# PolarizacionBJT.net
KiCad netlist of a schematic drawn in Altium Designer
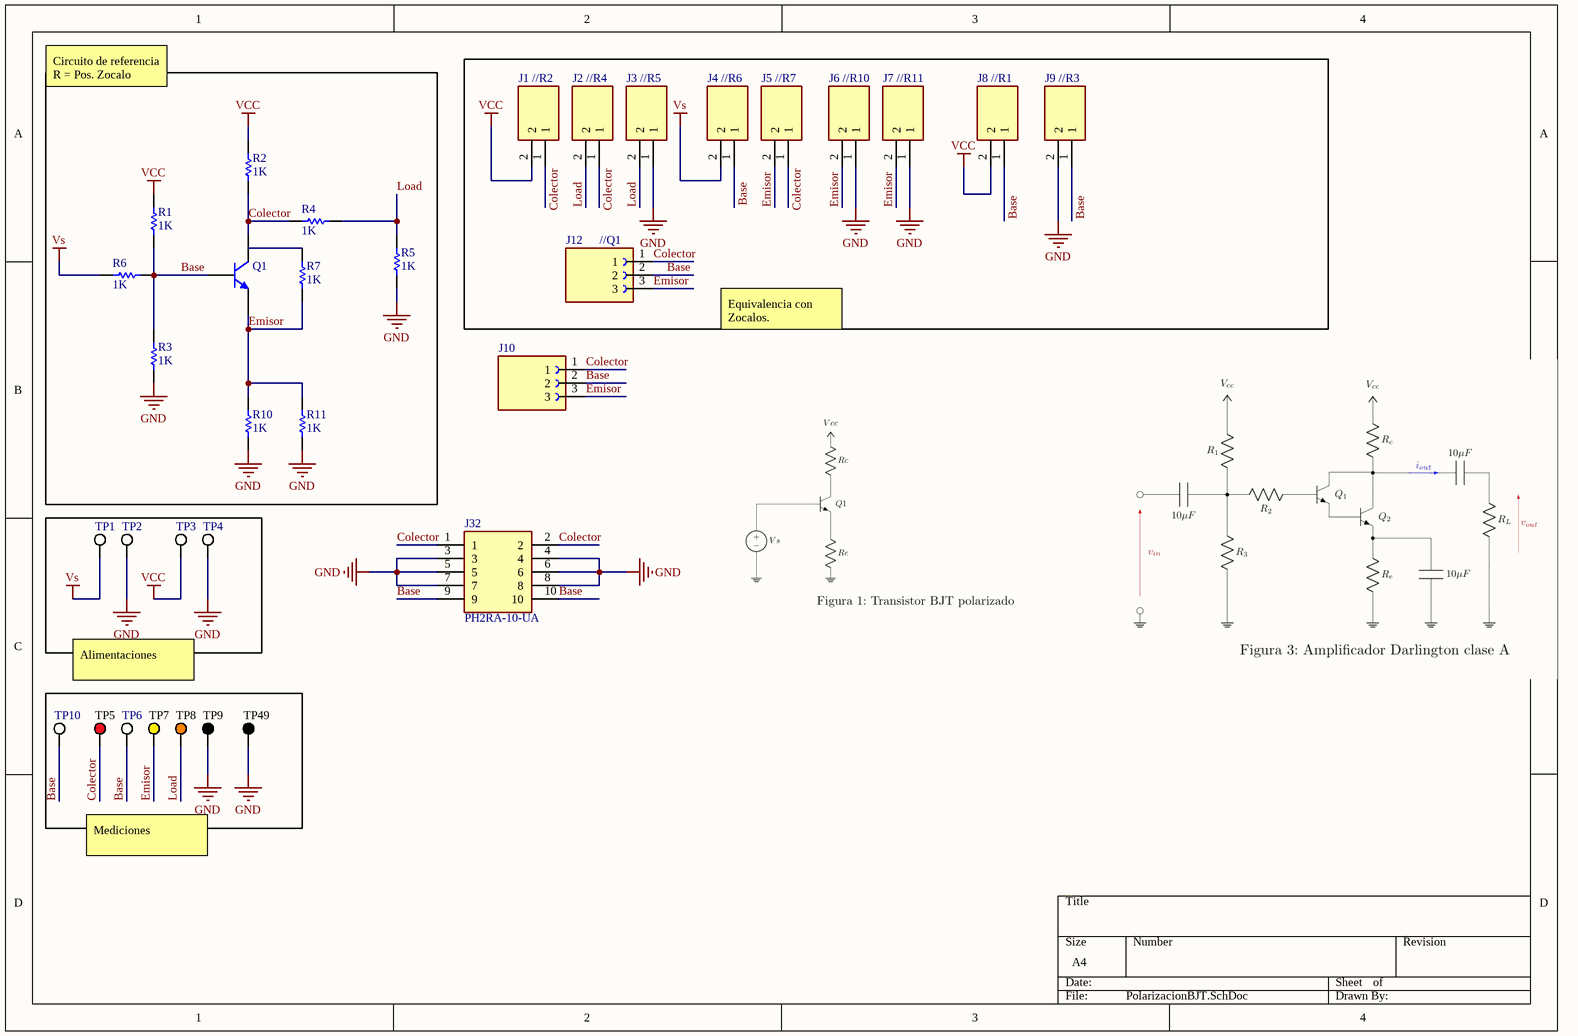
[diagram p0: PolarizacionBJT.SchDoc]

(export (version "E")
  (design (tool "Eeschema 10.0.6"))
  (components
    (comp (ref "J1")
      (value "D01-9970242")
      (footprint "D019970242")
      (description "IC Socket: 2 Pos Receptacle SIL Straight THT Strip")
      (fields (field (name "MOUSER PART NUMBER") "855-D01-9970242"))
      (libsource (lib "Zocalo_2pines") (part "D01-9970242"))
    )
    (comp (ref "J2")
      (value "D01-9970242")
      (footprint "D019970242")
      (description "IC Socket: 2 Pos Receptacle SIL Straight THT Strip")
      (fields (field (name "MOUSER PART NUMBER") "855-D01-9970242"))
      (libsource (lib "Zocalo_2pines") (part "D01-9970242"))
    )
    (comp (ref "J3")
      (value "D01-9970242")
      (footprint "D019970242")
      (description "IC Socket: 2 Pos Receptacle SIL Straight THT Strip")
      (fields (field (name "MOUSER PART NUMBER") "855-D01-9970242"))
      (libsource (lib "Zocalo_2pines") (part "D01-9970242"))
    )
    (comp (ref "J4")
      (value "D01-9970242")
      (footprint "D019970242")
      (description "IC Socket: 2 Pos Receptacle SIL Straight THT Strip")
      (fields (field (name "MOUSER PART NUMBER") "855-D01-9970242"))
      (libsource (lib "Zocalo_2pines") (part "D01-9970242"))
    )
    (comp (ref "J5")
      (value "D01-9970242")
      (footprint "D019970242")
      (description "IC Socket: 2 Pos Receptacle SIL Straight THT Strip")
      (fields (field (name "MOUSER PART NUMBER") "855-D01-9970242"))
      (libsource (lib "Zocalo_2pines") (part "D01-9970242"))
    )
    (comp (ref "J6")
      (value "D01-9970242")
      (footprint "D019970242")
      (description "IC Socket: 2 Pos Receptacle SIL Straight THT Strip")
      (fields (field (name "MOUSER PART NUMBER") "855-D01-9970242"))
      (libsource (lib "Zocalo_2pines") (part "D01-9970242"))
    )
    (comp (ref "J7")
      (value "D01-9970242")
      (footprint "D019970242")
      (description "IC Socket: 2 Pos Receptacle SIL Straight THT Strip")
      (fields (field (name "MOUSER PART NUMBER") "855-D01-9970242"))
      (libsource (lib "Zocalo_2pines") (part "D01-9970242"))
    )
    (comp (ref "J8")
      (value "D01-9970242")
      (footprint "D019970242")
      (description "IC Socket: 2 Pos Receptacle SIL Straight THT Strip")
      (fields (field (name "MOUSER PART NUMBER") "855-D01-9970242"))
      (libsource (lib "Zocalo_2pines") (part "D01-9970242"))
    )
    (comp (ref "J9")
      (value "D01-9970242")
      (footprint "D019970242")
      (description "IC Socket: 2 Pos Receptacle SIL Straight THT Strip")
      (fields (field (name "MOUSER PART NUMBER") "855-D01-9970242"))
      (libsource (lib "Zocalo_2pines") (part "D01-9970242"))
    )
    (comp (ref "J10")
      (value "D01-9970342")
      (footprint "HARWIN_D01-9970342")
      (libsource (lib "Zocalo_3pines") (part "D01-9970342"))
    )
    (comp (ref "J12")
      (value "D01-9970342")
      (footprint "HARWIN_D01-9970342")
      (libsource (lib "Zocalo_3pines") (part "D01-9970342"))
    )
    (comp (ref "J32")
      (value "PH2RA-10-UA")
      (footprint "HDRRA10W64P254_2X5_1270X250X538P")
      (description "CONN HEADER R/A 10POS 2.54MM")
      (fields (field (name "MOUSER PART NUMBER") "737-PH2RA-10-UA"))
      (libsource (lib "PH2RA-10-UA") (part "PH2RA-10-UA"))
    )
    (comp (ref "Q1")
      (value "Bipolar NPN 3 Pins Transistor VBIC Model")
      (libsource (lib "Simulation Generic Components") (part "BJT NPN VBIC"))
    )
    (comp (ref "R1")
      (value "1K")
      (description "Resistor")
      (libsource (lib "Simulation Generic Components") (part "Resistor"))
    )
    (comp (ref "R2")
      (value "1K")
      (description "Resistor")
      (libsource (lib "Simulation Generic Components") (part "Resistor"))
    )
    (comp (ref "R3")
      (value "1K")
      (description "Resistor")
      (libsource (lib "Simulation Generic Components") (part "Resistor"))
    )
    (comp (ref "R4")
      (value "1K")
      (description "Resistor")
      (libsource (lib "Simulation Generic Components") (part "Resistor"))
    )
    (comp (ref "R5")
      (value "1K")
      (description "Resistor")
      (libsource (lib "Simulation Generic Components") (part "Resistor"))
    )
    (comp (ref "R6")
      (value "1K")
      (description "Resistor")
      (libsource (lib "Simulation Generic Components") (part "Resistor"))
    )
    (comp (ref "R7")
      (value "1K")
      (description "Resistor")
      (libsource (lib "Simulation Generic Components") (part "Resistor"))
    )
    (comp (ref "R10")
      (value "1K")
      (description "Resistor")
      (libsource (lib "Simulation Generic Components") (part "Resistor"))
    )
    (comp (ref "R11")
      (value "1K")
      (description "Resistor")
      (libsource (lib "Simulation Generic Components") (part "Resistor"))
    )
    (comp (ref "TP1")
      (value "575-4")
      (footprint "KSTN-575-4")
      (description "Banana Jack, Non-Insulated, 1-Pin THD, RoHS, Bulk")
      (fields (field (name "MANUFACTURER") "Keystone-Electronics"))
      (libsource (lib "Altium Content Vault") (part "TESTPOINT_WHITE"))
    )
    (comp (ref "TP2")
      (value "575-4")
      (footprint "KSTN-575-4")
      (description "Banana Jack, Non-Insulated, 1-Pin THD, RoHS, Bulk")
      (fields (field (name "MANUFACTURER") "Keystone-Electronics"))
      (libsource (lib "Altium Content Vault") (part "TESTPOINT_WHITE"))
    )
    (comp (ref "TP3")
      (value "575-4")
      (footprint "KSTN-575-4")
      (description "Banana Jack, Non-Insulated, 1-Pin THD, RoHS, Bulk")
      (fields (field (name "MANUFACTURER") "Keystone-Electronics"))
      (libsource (lib "Altium Content Vault") (part "TESTPOINT_WHITE"))
    )
    (comp (ref "TP4")
      (value "575-4")
      (footprint "KSTN-575-4")
      (description "Banana Jack, Non-Insulated, 1-Pin THD, RoHS, Bulk")
      (fields (field (name "MANUFACTURER") "Keystone-Electronics"))
      (libsource (lib "Altium Content Vault") (part "TESTPOINT_WHITE"))
    )
    (comp (ref "TP5")
      (value "5010")
      (footprint "KSTN-5010_V")
      (description "Test Point, Red, Through Hole, RoHS, Bulk")
      (fields (field (name "MANUFACTURER") "Keystone"))
      (libsource (lib "Altium Content Vault") (part "TESTPOINT_RED"))
    )
    (comp (ref "TP6")
      (value "5012")
      (footprint "KSTN-5012_V")
      (description "Test Point, White, Through Hole, RoHS, Bulk")
      (fields (field (name "MANUFACTURER") "Keystone"))
      (libsource (lib "Altium Content Vault") (part "TESTPOINT_WHITE"))
    )
    (comp (ref "TP7")
      (value "5014")
      (footprint "KSTN-5014_V")
      (description "Test Point, Yellow, Through Hole, RoHS, Bulk")
      (fields (field (name "MANUFACTURER") "Keystone"))
      (libsource (lib "Altium Content Vault") (part "TESTPOINT_YELLOW"))
    )
    (comp (ref "TP8")
      (value "5013")
      (footprint "KSTN-5013_V")
      (description "Test Point, Orange, Through Hole, RoHS, Bulk")
      (fields (field (name "MANUFACTURER") "Keystone"))
      (libsource (lib "Altium Content Vault") (part "TESTPOINT_ORANGE"))
    )
    (comp (ref "TP9")
      (value "5011")
      (footprint "KSTN-5011_V")
      (description "Test Point, Black, Through Hole, RoHS, Bulk")
      (fields (field (name "MANUFACTURER") "Keystone"))
      (libsource (lib "Altium Content Vault") (part "TESTPOINT_BLACK"))
    )
    (comp (ref "TP10")
      (value "5012")
      (footprint "KSTN-5012_V")
      (description "Test Point, White, Through Hole, RoHS, Bulk")
      (fields (field (name "MANUFACTURER") "Keystone"))
      (libsource (lib "Altium Content Vault") (part "TESTPOINT_WHITE"))
    )
    (comp (ref "TP49")
      (value "5011")
      (footprint "KSTN-5011_V")
      (description "Test Point, Black, Through Hole, RoHS, Bulk")
      (fields (field (name "MANUFACTURER") "Keystone"))
      (libsource (lib "Altium Content Vault") (part "TESTPOINT_BLACK"))
    )
  )
  (nets
    (net (code "1") (name "/Base") (class "Default")
      (node (ref "J10") (pin "2") (pinfunction "2_2") (pintype "passive"))
      (node (ref "J12") (pin "2") (pinfunction "2_2") (pintype "passive"))
      (node (ref "J32") (pin "10") (pinfunction "10_10") (pintype "passive"))
      (node (ref "J32") (pin "9") (pinfunction "9_9") (pintype "passive"))
      (node (ref "J4") (pin "1") (pinfunction "1_1") (pintype "passive"))
      (node (ref "J8") (pin "1") (pinfunction "1_1") (pintype "passive"))
      (node (ref "J9") (pin "1") (pinfunction "1_1") (pintype "passive"))
      (node (ref "Q1") (pin "2") (pinfunction "B_2") (pintype "passive"))
      (node (ref "R1") (pin "1") (pinfunction "1_1") (pintype "passive"))
      (node (ref "R3") (pin "2") (pinfunction "2_2") (pintype "passive"))
      (node (ref "R6") (pin "1") (pinfunction "1_1") (pintype "passive"))
      (node (ref "TP10") (pin "1") (pinfunction "1_1") (pintype "passive"))
      (node (ref "TP6") (pin "1") (pinfunction "1_1") (pintype "passive"))
    )
    (net (code "2") (name "/Colector") (class "Default")
      (node (ref "J1") (pin "1") (pinfunction "1_1") (pintype "passive"))
      (node (ref "J10") (pin "1") (pinfunction "1_1") (pintype "passive"))
      (node (ref "J12") (pin "1") (pinfunction "1_1") (pintype "passive"))
      (node (ref "J2") (pin "1") (pinfunction "1_1") (pintype "passive"))
      (node (ref "J32") (pin "1") (pinfunction "1_1") (pintype "passive"))
      (node (ref "J32") (pin "2") (pinfunction "2_2") (pintype "passive"))
      (node (ref "J5") (pin "1") (pinfunction "1_1") (pintype "passive"))
      (node (ref "Q1") (pin "1") (pinfunction "C_1") (pintype "passive"))
      (node (ref "R2") (pin "2") (pinfunction "2_2") (pintype "passive"))
      (node (ref "R4") (pin "2") (pinfunction "2_2") (pintype "passive"))
      (node (ref "TP5") (pin "1") (pinfunction "1_1") (pintype "passive"))
    )
    (net (code "3") (name "/Emisor") (class "Default")
      (node (ref "J10") (pin "3") (pinfunction "3_3") (pintype "passive"))
      (node (ref "J12") (pin "3") (pinfunction "3_3") (pintype "passive"))
      (node (ref "J5") (pin "2") (pinfunction "2_2") (pintype "passive"))
      (node (ref "J6") (pin "2") (pinfunction "2_2") (pintype "passive"))
      (node (ref "J7") (pin "2") (pinfunction "2_2") (pintype "passive"))
      (node (ref "Q1") (pin "3") (pinfunction "E_3") (pintype "passive"))
      (node (ref "R10") (pin "1") (pinfunction "1_1") (pintype "passive"))
      (node (ref "R11") (pin "1") (pinfunction "1_1") (pintype "passive"))
      (node (ref "R7") (pin "2") (pinfunction "2_2") (pintype "passive"))
      (node (ref "TP7") (pin "1") (pinfunction "1_1") (pintype "passive"))
    )
    (net (code "4") (name "/Load") (class "Default")
      (node (ref "J2") (pin "2") (pinfunction "2_2") (pintype "passive"))
      (node (ref "J3") (pin "2") (pinfunction "2_2") (pintype "passive"))
      (node (ref "R4") (pin "1") (pinfunction "1_1") (pintype "passive"))
      (node (ref "R5") (pin "1") (pinfunction "1_1") (pintype "passive"))
      (node (ref "TP8") (pin "1") (pinfunction "1_1") (pintype "passive"))
    )
    (net (code "5") (name "GND") (class "Default")
      (node (ref "J3") (pin "1") (pinfunction "1_1") (pintype "passive"))
      (node (ref "J32") (pin "3") (pinfunction "3_3") (pintype "passive"))
      (node (ref "J32") (pin "4") (pinfunction "4_4") (pintype "passive"))
      (node (ref "J32") (pin "5") (pinfunction "5_5") (pintype "passive"))
      (node (ref "J32") (pin "6") (pinfunction "6_6") (pintype "passive"))
      (node (ref "J32") (pin "7") (pinfunction "7_7") (pintype "passive"))
      (node (ref "J32") (pin "8") (pinfunction "8_8") (pintype "passive"))
      (node (ref "J6") (pin "1") (pinfunction "1_1") (pintype "passive"))
      (node (ref "J7") (pin "1") (pinfunction "1_1") (pintype "passive"))
      (node (ref "J9") (pin "2") (pinfunction "2_2") (pintype "passive"))
      (node (ref "R10") (pin "2") (pinfunction "2_2") (pintype "passive"))
      (node (ref "R11") (pin "2") (pinfunction "2_2") (pintype "passive"))
      (node (ref "R3") (pin "1") (pinfunction "1_1") (pintype "passive"))
      (node (ref "R5") (pin "2") (pinfunction "2_2") (pintype "passive"))
      (node (ref "TP2") (pin "1") (pinfunction "1_1") (pintype "passive"))
      (node (ref "TP4") (pin "1") (pinfunction "1_1") (pintype "passive"))
      (node (ref "TP49") (pin "1") (pinfunction "1_1") (pintype "passive"))
      (node (ref "TP9") (pin "1") (pinfunction "1_1") (pintype "passive"))
    )
    (net (code "6") (name "VCC") (class "Default")
      (node (ref "J1") (pin "2") (pinfunction "2_2") (pintype "passive"))
      (node (ref "J8") (pin "2") (pinfunction "2_2") (pintype "passive"))
      (node (ref "R1") (pin "2") (pinfunction "2_2") (pintype "passive"))
      (node (ref "R2") (pin "1") (pinfunction "1_1") (pintype "passive"))
      (node (ref "TP3") (pin "1") (pinfunction "1_1") (pintype "passive"))
    )
    (net (code "7") (name "Vs") (class "Default")
      (node (ref "J4") (pin "2") (pinfunction "2_2") (pintype "passive"))
      (node (ref "R6") (pin "2") (pinfunction "2_2") (pintype "passive"))
      (node (ref "TP1") (pin "1") (pinfunction "1_1") (pintype "passive"))
    )
    (net (code "8") (name "unconnected-(R7-Pad1)") (class "Default")
      (node (ref "R7") (pin "1") (pinfunction "1_1") (pintype "passive"))
    )
  )
)
